# attiny_shiftOut.net
KiCad netlist of a schematic drawn in EAGLE
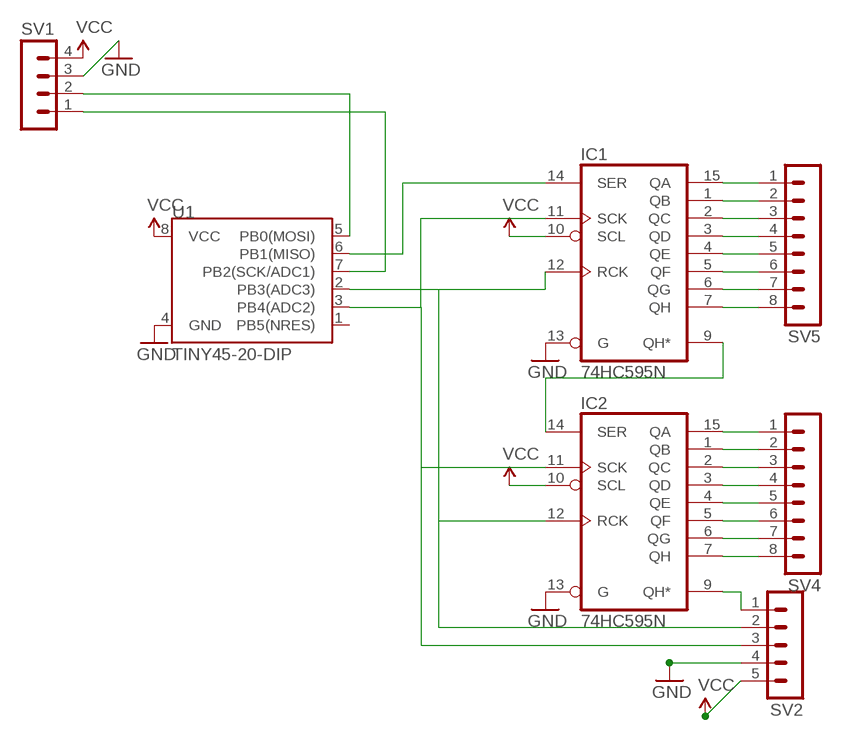
[diagram p0: schematic, sheet 1]

(export (version "E")
  (design (tool "Eeschema 10.0.6"))
  (components
    (comp (ref "IC1")
      (value "74HC595N")
      (footprint "eagle-import:DIL16")
      (libsource (lib "eagle-import") (part "74595NHC"))
    )
    (comp (ref "IC2")
      (value "74HC595N")
      (footprint "eagle-import:DIL16")
      (libsource (lib "eagle-import") (part "74595NHC"))
    )
    (comp (ref "SV1")
      (value "MA04-1")
      (footprint "eagle-import:MA04-1")
      (libsource (lib "eagle-import") (part "MA04-1"))
    )
    (comp (ref "SV2")
      (value "MA05-1")
      (footprint "eagle-import:MA05-1")
      (libsource (lib "eagle-import") (part "MA05-1"))
    )
    (comp (ref "SV4")
      (value "MA08-1")
      (footprint "eagle-import:MA08-1")
      (libsource (lib "eagle-import") (part "MA08-1"))
    )
    (comp (ref "SV5")
      (value "MA08-1")
      (footprint "eagle-import:MA08-1")
      (libsource (lib "eagle-import") (part "MA08-1"))
    )
    (comp (ref "U1")
      (value "TINY45-20-DIP")
      (footprint "eagle-import:DIP08")
      (libsource (lib "eagle-import") (part "ATTINY45TINY45-20-DIP"))
    )
  )
  (nets
    (net (code "1") (name "GND") (class "Default")
      (node (ref "IC1") (pin "13") (pinfunction "G_13") (pintype "input"))
      (node (ref "IC2") (pin "13") (pinfunction "G_13") (pintype "input"))
      (node (ref "SV1") (pin "3") (pinfunction "3_3") (pintype "passive"))
      (node (ref "SV2") (pin "4") (pinfunction "4_4") (pintype "passive"))
      (node (ref "U1") (pin "4") (pinfunction "GND_4") (pintype "bidirectional"))
    )
    (net (code "2") (name "Net-(IC1A-QA)") (class "Default")
      (node (ref "IC1") (pin "15") (pinfunction "QA_15") (pintype "tri_state"))
      (node (ref "SV5") (pin "1") (pinfunction "1_1") (pintype "passive"))
    )
    (net (code "3") (name "Net-(IC1A-QB)") (class "Default")
      (node (ref "IC1") (pin "1") (pinfunction "QB_1") (pintype "tri_state"))
      (node (ref "SV5") (pin "2") (pinfunction "2_2") (pintype "passive"))
    )
    (net (code "4") (name "Net-(IC1A-QC)") (class "Default")
      (node (ref "IC1") (pin "2") (pinfunction "QC_2") (pintype "tri_state"))
      (node (ref "SV5") (pin "3") (pinfunction "3_3") (pintype "passive"))
    )
    (net (code "5") (name "Net-(IC1A-QD)") (class "Default")
      (node (ref "IC1") (pin "3") (pinfunction "QD_3") (pintype "tri_state"))
      (node (ref "SV5") (pin "4") (pinfunction "4_4") (pintype "passive"))
    )
    (net (code "6") (name "Net-(IC1A-QE)") (class "Default")
      (node (ref "IC1") (pin "4") (pinfunction "QE_4") (pintype "tri_state"))
      (node (ref "SV5") (pin "5") (pinfunction "5_5") (pintype "passive"))
    )
    (net (code "7") (name "Net-(IC1A-QF)") (class "Default")
      (node (ref "IC1") (pin "5") (pinfunction "QF_5") (pintype "tri_state"))
      (node (ref "SV5") (pin "6") (pinfunction "6_6") (pintype "passive"))
    )
    (net (code "8") (name "Net-(IC1A-QG)") (class "Default")
      (node (ref "IC1") (pin "6") (pinfunction "QG_6") (pintype "tri_state"))
      (node (ref "SV5") (pin "7") (pinfunction "7_7") (pintype "passive"))
    )
    (net (code "9") (name "Net-(IC1A-QH)") (class "Default")
      (node (ref "IC1") (pin "7") (pinfunction "QH_7") (pintype "tri_state"))
      (node (ref "SV5") (pin "8") (pinfunction "8_8") (pintype "passive"))
    )
    (net (code "10") (name "Net-(IC1A-QH*)") (class "Default")
      (node (ref "IC1") (pin "9") (pinfunction "QH*_9") (pintype "tri_state"))
      (node (ref "IC2") (pin "14") (pinfunction "SER_14") (pintype "input"))
    )
    (net (code "11") (name "Net-(IC1A-RCK)") (class "Default")
      (node (ref "IC1") (pin "12") (pinfunction "RCK_12") (pintype "input"))
      (node (ref "IC2") (pin "12") (pinfunction "RCK_12") (pintype "input"))
      (node (ref "SV2") (pin "2") (pinfunction "2_2") (pintype "passive"))
      (node (ref "U1") (pin "2") (pinfunction "PB3(ADC3)_2") (pintype "bidirectional"))
    )
    (net (code "12") (name "Net-(IC1A-SCK)") (class "Default")
      (node (ref "IC1") (pin "11") (pinfunction "SCK_11") (pintype "input"))
      (node (ref "IC2") (pin "11") (pinfunction "SCK_11") (pintype "input"))
      (node (ref "SV2") (pin "3") (pinfunction "3_3") (pintype "passive"))
      (node (ref "U1") (pin "3") (pinfunction "PB4(ADC2)_3") (pintype "bidirectional"))
    )
    (net (code "13") (name "Net-(IC1A-SER)") (class "Default")
      (node (ref "IC1") (pin "14") (pinfunction "SER_14") (pintype "input"))
      (node (ref "U1") (pin "6") (pinfunction "PB1(MISO)_6") (pintype "bidirectional"))
    )
    (net (code "14") (name "Net-(IC2A-QA)") (class "Default")
      (node (ref "IC2") (pin "15") (pinfunction "QA_15") (pintype "tri_state"))
      (node (ref "SV4") (pin "1") (pinfunction "1_1") (pintype "passive"))
    )
    (net (code "15") (name "Net-(IC2A-QB)") (class "Default")
      (node (ref "IC2") (pin "1") (pinfunction "QB_1") (pintype "tri_state"))
      (node (ref "SV4") (pin "2") (pinfunction "2_2") (pintype "passive"))
    )
    (net (code "16") (name "Net-(IC2A-QC)") (class "Default")
      (node (ref "IC2") (pin "2") (pinfunction "QC_2") (pintype "tri_state"))
      (node (ref "SV4") (pin "3") (pinfunction "3_3") (pintype "passive"))
    )
    (net (code "17") (name "Net-(IC2A-QD)") (class "Default")
      (node (ref "IC2") (pin "3") (pinfunction "QD_3") (pintype "tri_state"))
      (node (ref "SV4") (pin "4") (pinfunction "4_4") (pintype "passive"))
    )
    (net (code "18") (name "Net-(IC2A-QE)") (class "Default")
      (node (ref "IC2") (pin "4") (pinfunction "QE_4") (pintype "tri_state"))
      (node (ref "SV4") (pin "5") (pinfunction "5_5") (pintype "passive"))
    )
    (net (code "19") (name "Net-(IC2A-QF)") (class "Default")
      (node (ref "IC2") (pin "5") (pinfunction "QF_5") (pintype "tri_state"))
      (node (ref "SV4") (pin "6") (pinfunction "6_6") (pintype "passive"))
    )
    (net (code "20") (name "Net-(IC2A-QG)") (class "Default")
      (node (ref "IC2") (pin "6") (pinfunction "QG_6") (pintype "tri_state"))
      (node (ref "SV4") (pin "7") (pinfunction "7_7") (pintype "passive"))
    )
    (net (code "21") (name "Net-(IC2A-QH)") (class "Default")
      (node (ref "IC2") (pin "7") (pinfunction "QH_7") (pintype "tri_state"))
      (node (ref "SV4") (pin "8") (pinfunction "8_8") (pintype "passive"))
    )
    (net (code "22") (name "Net-(IC2A-QH*)") (class "Default")
      (node (ref "IC2") (pin "9") (pinfunction "QH*_9") (pintype "tri_state"))
      (node (ref "SV2") (pin "1") (pinfunction "1_1") (pintype "passive"))
    )
    (net (code "23") (name "Net-(U1-PB0(MOSI))") (class "Default")
      (node (ref "SV1") (pin "2") (pinfunction "2_2") (pintype "passive"))
      (node (ref "U1") (pin "5") (pinfunction "PB0(MOSI)_5") (pintype "bidirectional"))
    )
    (net (code "24") (name "Net-(U1-PB2(SCK{slash}ADC1))") (class "Default")
      (node (ref "SV1") (pin "1") (pinfunction "1_1") (pintype "passive"))
      (node (ref "U1") (pin "7") (pinfunction "PB2(SCK/ADC1)_7") (pintype "bidirectional"))
    )
    (net (code "25") (name "VCC") (class "Default")
      (node (ref "IC1") (pin "10") (pinfunction "SCL_10") (pintype "input"))
      (node (ref "IC2") (pin "10") (pinfunction "SCL_10") (pintype "input"))
      (node (ref "SV1") (pin "4") (pinfunction "4_4") (pintype "passive"))
      (node (ref "SV2") (pin "5") (pinfunction "5_5") (pintype "passive"))
      (node (ref "U1") (pin "8") (pinfunction "VCC_8") (pintype "bidirectional"))
    )
    (net (code "26") (name "unconnected-(U1-PB5(NRES)-Pad1)") (class "Default")
      (node (ref "U1") (pin "1") (pinfunction "PB5(NRES)_1") (pintype "bidirectional"))
    )
  )
)
